# power.net
KiCad netlist of a schematic drawn in Altium Designer
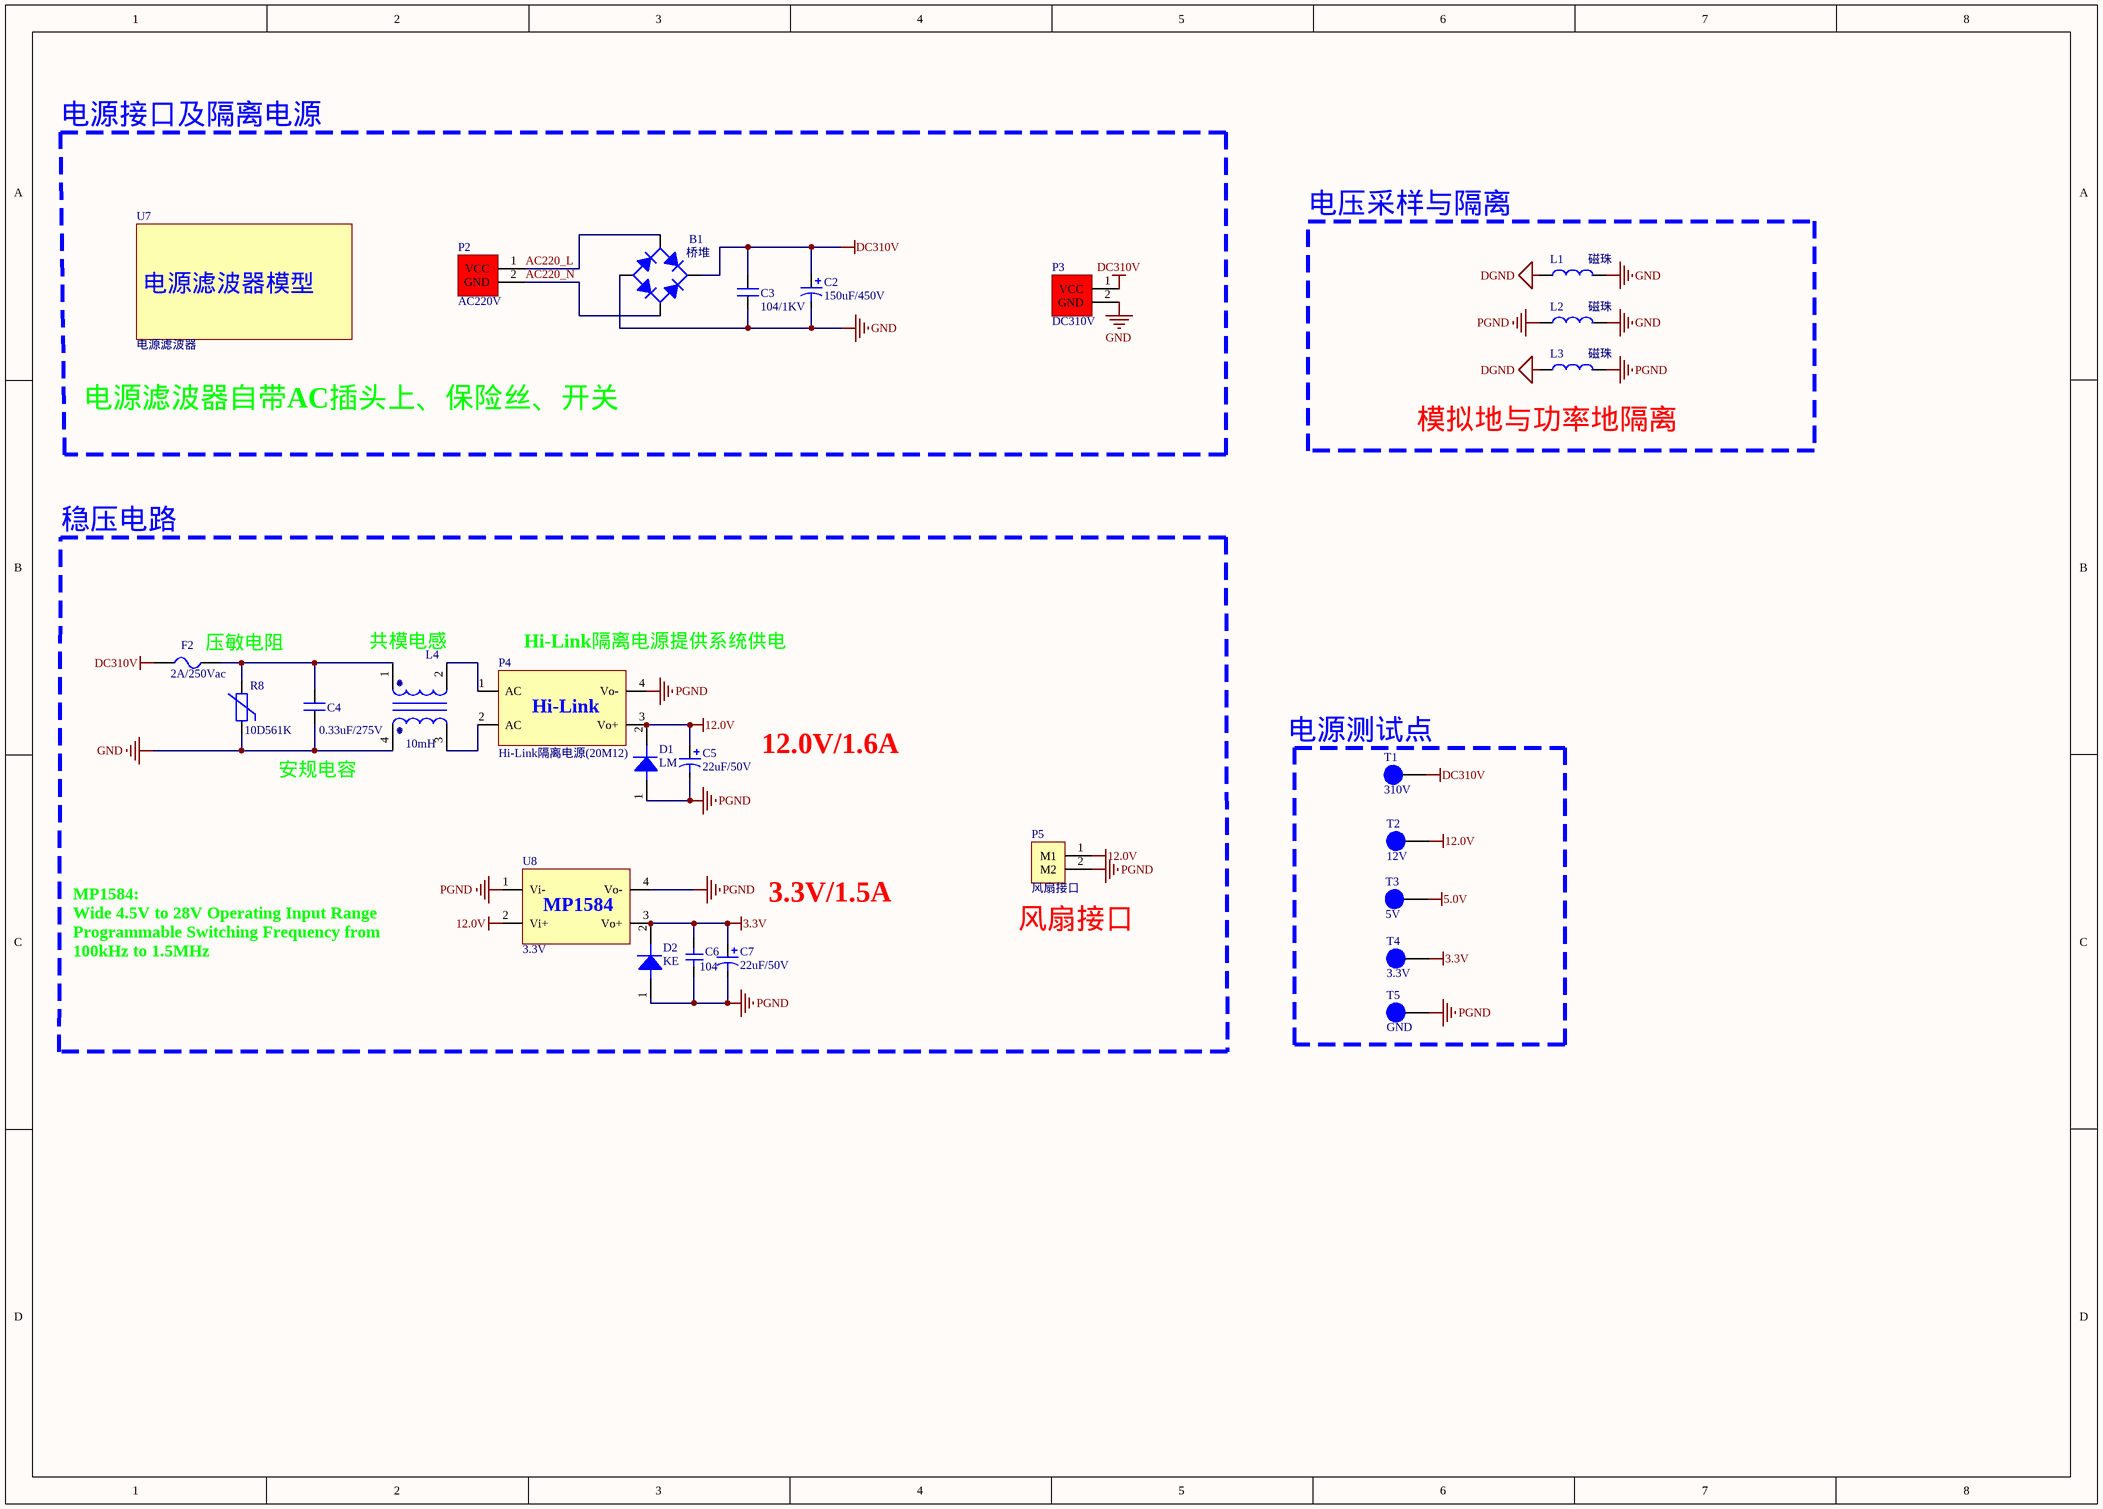
[diagram p0: power.SchDoc]

(export (version "E")
  (design (tool "Eeschema 10.0.6"))
  (components
    (comp (ref "B1") (value "桥堆") (footprint "KBPC1010") (libsource (lib "Mylib") (part "桥堆")))
    (comp (ref "C2")
      (value "150uF/450V")
      (footprint "CAP 7.5*18*35.5-H - BK")
      (description "直插极性电容")
      (libsource (lib "Mylib") (part "Cap3"))
    )
    (comp (ref "C3")
      (value "104/1KV")
      (footprint "CY 5*7*2.5")
      (description "无极直插电容")
      (libsource (lib "Mylib") (part "Cap2"))
    )
    (comp (ref "C4")
      (value "0.33uF/275V")
      (footprint "安规电容 x2v-18w15h5-9t5-p15")
      (description "无极直插电容")
      (libsource (lib "Mylib") (part "Cap2"))
    )
    (comp (ref "C5")
      (value "22uF/50V")
      (footprint "CM D(6.3*5.4)")
      (description "直插极性电容")
      (libsource (lib "集大电协1.5") (part "Cap3"))
    )
    (comp (ref "C6")
      (value "104")
      (footprint "0805C")
      (description "无极贴片电容")
      (libsource (lib "Mylib") (part "Cap1"))
    )
    (comp (ref "C7")
      (value "22uF/50V")
      (footprint "CM D(6.3*5.4)")
      (description "直插极性电容")
      (libsource (lib "集大电协1.5") (part "Cap3"))
    )
    (comp (ref "D1")
      (value "LM")
      (footprint "SMA")
      (description "二极管")
      (libsource (lib "集大电协1.5") (part "Diode"))
    )
    (comp (ref "D2")
      (value "KE")
      (footprint "SMA")
      (description "二极管")
      (libsource (lib "集大电协1.5") (part "Diode"))
    )
    (comp (ref "F2")
      (value "2A/250Vac")
      (footprint "FU 5x20")
      (description "保险丝")
      (libsource (lib "集大电协1.5") (part "Fuse"))
    )
    (comp (ref "L1")
      (value "磁珠")
      (footprint "1206L")
      (description "电感")
      (libsource (lib "集大电协1.5") (part "L"))
    )
    (comp (ref "L2")
      (value "磁珠")
      (footprint "1206L")
      (description "电感")
      (libsource (lib "集大电协1.5") (part "L"))
    )
    (comp (ref "L3")
      (value "磁珠")
      (footprint "1206L")
      (description "电感")
      (libsource (lib "集大电协1.5") (part "L"))
    )
    (comp (ref "L4") (value "10mH") (footprint "T12x6x4") (libsource (lib "集大电协1.5") (part "共模电感")))
    (comp (ref "P2") (value "AC220V") (footprint "XT30-F") (libsource (lib "Mylib") (part "电源端子")))
    (comp (ref "P3") (value "DC310V") (footprint "XT30-F") (libsource (lib "Mylib") (part "电源端子")))
    (comp (ref "P4")
      (value "Hi-Link隔离电源(20M12)")
      (footprint "HLK-20M24")
      (libsource (lib "集大电协1.5") (part "HILINK-24V"))
    )
    (comp (ref "P5")
      (value "风扇接口")
      (footprint "XH2/2.54mm/180")
      (description "2PIN")
      (libsource (lib "Mylib") (part "接线端子-2PIN"))
    )
    (comp (ref "R8") (value "10D561K") (footprint "VDR 10D-4.5") (libsource (lib "集大电协1.5") (part "压敏电阻")))
    (comp (ref "T1")
      (value "310V")
      (footprint "HEADER 1")
      (description "测试点")
      (libsource (lib "集大电协1.2") (part "测试点"))
    )
    (comp (ref "T2")
      (value "12V")
      (footprint "HEADER 1")
      (description "测试点")
      (libsource (lib "集大电协1.2") (part "测试点"))
    )
    (comp (ref "T3")
      (value "5V")
      (footprint "HEADER 1")
      (description "测试点")
      (libsource (lib "集大电协1.2") (part "测试点"))
    )
    (comp (ref "T4")
      (value "3.3V")
      (footprint "HEADER 1")
      (description "测试点")
      (libsource (lib "集大电协1.2") (part "测试点"))
    )
    (comp (ref "T5")
      (value "GND")
      (footprint "HEADER 1")
      (description "测试点")
      (libsource (lib "集大电协1.2") (part "测试点"))
    )
    (comp (ref "U7")
      (value "电源滤波器")
      (footprint "电源滤波器绿灯开关双保险")
      (libsource (lib "Mylib") (part "电源滤波器绿灯开关双保险"))
    )
    (comp (ref "U8") (value "3.3V") (footprint "MP1584电源模块") (libsource (lib "集大电协1.5") (part "MP1584电源模块")))
  )
  (nets
    (net (code "1") (name "/AC220_L") (class "Default")
      (node (ref "B1") (pin "AC1") (pinfunction "AC1_AC1") (pintype "passive"))
      (node (ref "P2") (pin "1") (pinfunction "VCC_1") (pintype "passive"))
    )
    (net (code "2") (name "/AC220_N") (class "Default")
      (node (ref "B1") (pin "AC2") (pinfunction "AC2_AC2") (pintype "passive"))
      (node (ref "P2") (pin "2") (pinfunction "GND_2") (pintype "passive"))
    )
    (net (code "3") (name "3.3V") (class "Default")
      (node (ref "C6") (pin "2") (pinfunction "2_2") (pintype "passive"))
      (node (ref "C7") (pin "1") (pinfunction "1_1") (pintype "passive"))
      (node (ref "D2") (pin "2") (pinfunction "2_2") (pintype "passive"))
      (node (ref "T4") (pin "1") (pinfunction "1_1") (pintype "passive"))
      (node (ref "U8") (pin "3") (pinfunction "Vo+_3") (pintype "passive"))
    )
    (net (code "4") (name "5.0V") (class "Default")
      (node (ref "T3") (pin "1") (pinfunction "1_1") (pintype "passive"))
    )
    (net (code "5") (name "12.0V") (class "Default")
      (node (ref "C5") (pin "1") (pinfunction "1_1") (pintype "passive"))
      (node (ref "D1") (pin "2") (pinfunction "2_2") (pintype "passive"))
      (node (ref "P4") (pin "3") (pinfunction "Vo+_3") (pintype "passive"))
      (node (ref "P5") (pin "1") (pinfunction "M1_1") (pintype "passive"))
      (node (ref "T2") (pin "1") (pinfunction "1_1") (pintype "passive"))
      (node (ref "U8") (pin "2") (pinfunction "Vi+_2") (pintype "passive"))
    )
    (net (code "6") (name "DC310V") (class "Default")
      (node (ref "B1") (pin "DC+") (pinfunction "DC+_DC+") (pintype "passive"))
      (node (ref "C2") (pin "1") (pinfunction "1_1") (pintype "passive"))
      (node (ref "C3") (pin "2") (pinfunction "2_2") (pintype "passive"))
      (node (ref "F2") (pin "1") (pinfunction "1_1") (pintype "passive"))
      (node (ref "P3") (pin "1") (pinfunction "VCC_1") (pintype "passive"))
      (node (ref "T1") (pin "1") (pinfunction "1_1") (pintype "passive"))
    )
    (net (code "7") (name "DGND") (class "Default")
      (node (ref "L1") (pin "1") (pinfunction "1_1") (pintype "passive"))
      (node (ref "L3") (pin "1") (pinfunction "1_1") (pintype "passive"))
    )
    (net (code "8") (name "GND") (class "Default")
      (node (ref "B1") (pin "DC-") (pinfunction "DC-_DC-") (pintype "passive"))
      (node (ref "C2") (pin "2") (pinfunction "2_2") (pintype "passive"))
      (node (ref "C3") (pin "1") (pinfunction "1_1") (pintype "passive"))
      (node (ref "C4") (pin "1") (pinfunction "1_1") (pintype "passive"))
      (node (ref "L1") (pin "2") (pinfunction "2_2") (pintype "passive"))
      (node (ref "L2") (pin "2") (pinfunction "2_2") (pintype "passive"))
      (node (ref "L4") (pin "4") (pinfunction "4_4") (pintype "passive"))
      (node (ref "P3") (pin "2") (pinfunction "GND_2") (pintype "passive"))
      (node (ref "R8") (pin "1") (pinfunction "1_1") (pintype "passive"))
    )
    (net (code "9") (name "Net-(C4-Pad2)") (class "Default")
      (node (ref "C4") (pin "2") (pinfunction "2_2") (pintype "passive"))
      (node (ref "F2") (pin "2") (pinfunction "2_2") (pintype "passive"))
      (node (ref "L4") (pin "1") (pinfunction "1_1") (pintype "passive"))
      (node (ref "R8") (pin "2") (pinfunction "2_2") (pintype "passive"))
    )
    (net (code "10") (name "Net-(L4-Pad2)") (class "Default")
      (node (ref "L4") (pin "2") (pinfunction "2_2") (pintype "passive"))
      (node (ref "P4") (pin "1") (pinfunction "AC_1") (pintype "passive"))
    )
    (net (code "11") (name "Net-(L4-Pad3)") (class "Default")
      (node (ref "L4") (pin "3") (pinfunction "3_3") (pintype "passive"))
      (node (ref "P4") (pin "2") (pinfunction "AC_2") (pintype "passive"))
    )
    (net (code "12") (name "PGND") (class "Default")
      (node (ref "C5") (pin "2") (pinfunction "2_2") (pintype "passive"))
      (node (ref "C6") (pin "1") (pinfunction "1_1") (pintype "passive"))
      (node (ref "C7") (pin "2") (pinfunction "2_2") (pintype "passive"))
      (node (ref "D1") (pin "1") (pintype "passive"))
      (node (ref "D2") (pin "1") (pintype "passive"))
      (node (ref "L2") (pin "1") (pinfunction "1_1") (pintype "passive"))
      (node (ref "L3") (pin "2") (pinfunction "2_2") (pintype "passive"))
      (node (ref "P4") (pin "4") (pinfunction "Vo-_4") (pintype "passive"))
      (node (ref "P5") (pin "2") (pinfunction "M2_2") (pintype "passive"))
      (node (ref "T5") (pin "1") (pinfunction "1_1") (pintype "passive"))
      (node (ref "U8") (pin "1") (pinfunction "Vi-_1") (pintype "passive"))
      (node (ref "U8") (pin "4") (pinfunction "Vo-_4") (pintype "passive"))
    )
  )
)
